# Fiber_interlock.net
KiCad netlist of a schematic drawn in Altium Designer
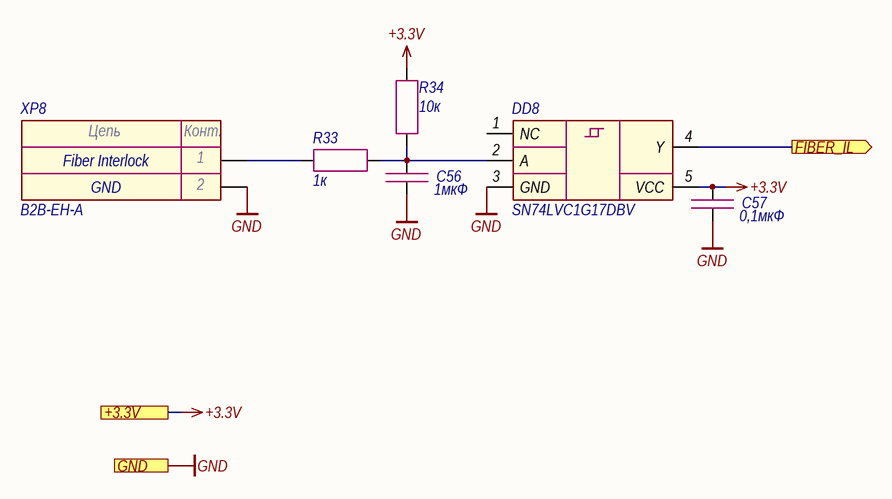
[diagram p0: Fiber_interlock.SchDoc]

(export (version "E")
  (design (tool "Eeschema 10.0.6"))
  (components
    (comp (ref "C56")
      (value "1мкФ")
      (footprint "Pcb_library:CAP_0603")
      (fields (field (name "MANUFACTURER") "Murata"))
      (libsource (lib "Schem_library") (part "Capacitor"))
    )
    (comp (ref "C57")
      (value "0,1мкФ")
      (footprint "Pcb_library:CAP_0603")
      (fields (field (name "MANUFACTURER") "Murata"))
      (libsource (lib "Schem_library") (part "Capacitor"))
    )
    (comp (ref "DD8")
      (value "SN74LVC1G17DBV")
      (footprint "Pcb_library:SOT-23-5")
      (fields (field (name "MANUFACTURER") "Texas Instruments"))
      (libsource (lib "Schem_library") (part "SN74LVC1G17"))
    )
    (comp (ref "R33")
      (value "1к")
      (footprint "Pcb_library:RES_0603")
      (fields (field (name "MANUFACTURER") "Yageo"))
      (libsource (lib "Schem_library") (part "Resistor"))
    )
    (comp (ref "R34")
      (value "10к")
      (footprint "Pcb_library:RES_0603")
      (fields (field (name "MANUFACTURER") "Yageo"))
      (libsource (lib "Schem_library") (part "Resistor"))
    )
    (comp (ref "XP8")
      (value "B2B-EH-A")
      (footprint "Pcb_library:B2B-EH-A")
      (fields (field (name "MANUFACTURER") "JST"))
      (libsource (lib "Schem_library") (part "Connector-2"))
    )
  )
  (nets
    (net (code "1") (name "+3.3V") (class "Default")
      (node (ref "C57") (pin "1") (pinfunction "1_1") (pintype "passive"))
      (node (ref "DD8") (pin "5") (pinfunction "VCC_5") (pintype "passive"))
      (node (ref "R34") (pin "2") (pinfunction "2_2") (pintype "passive"))
    )
    (net (code "2") (name "/FIBER_IL") (class "Default")
      (node (ref "DD8") (pin "4") (pinfunction "Y_4") (pintype "passive"))
    )
    (net (code "3") (name "GND") (class "Default")
      (node (ref "C56") (pin "2") (pinfunction "2_2") (pintype "passive"))
      (node (ref "C57") (pin "2") (pinfunction "2_2") (pintype "passive"))
      (node (ref "DD8") (pin "3") (pinfunction "GND_3") (pintype "passive"))
      (node (ref "XP8") (pin "2") (pintype "passive"))
    )
    (net (code "4") (name "Net-(DD8-A)") (class "Default")
      (node (ref "C56") (pin "1") (pinfunction "1_1") (pintype "passive"))
      (node (ref "DD8") (pin "2") (pinfunction "A_2") (pintype "passive"))
      (node (ref "R33") (pin "2") (pinfunction "2_2") (pintype "passive"))
      (node (ref "R34") (pin "1") (pinfunction "1_1") (pintype "passive"))
    )
    (net (code "5") (name "Net-(R33-Pad1)") (class "Default")
      (node (ref "R33") (pin "1") (pinfunction "1_1") (pintype "passive"))
      (node (ref "XP8") (pin "1") (pintype "passive"))
    )
    (net (code "6") (name "unconnected-(DD8-NC-Pad1)") (class "Default")
      (node (ref "DD8") (pin "1") (pinfunction "NC_1") (pintype "passive"))
    )
  )
)
